# 384X_PWMMOD.net
KiCad netlist of a schematic drawn in Altium Designer
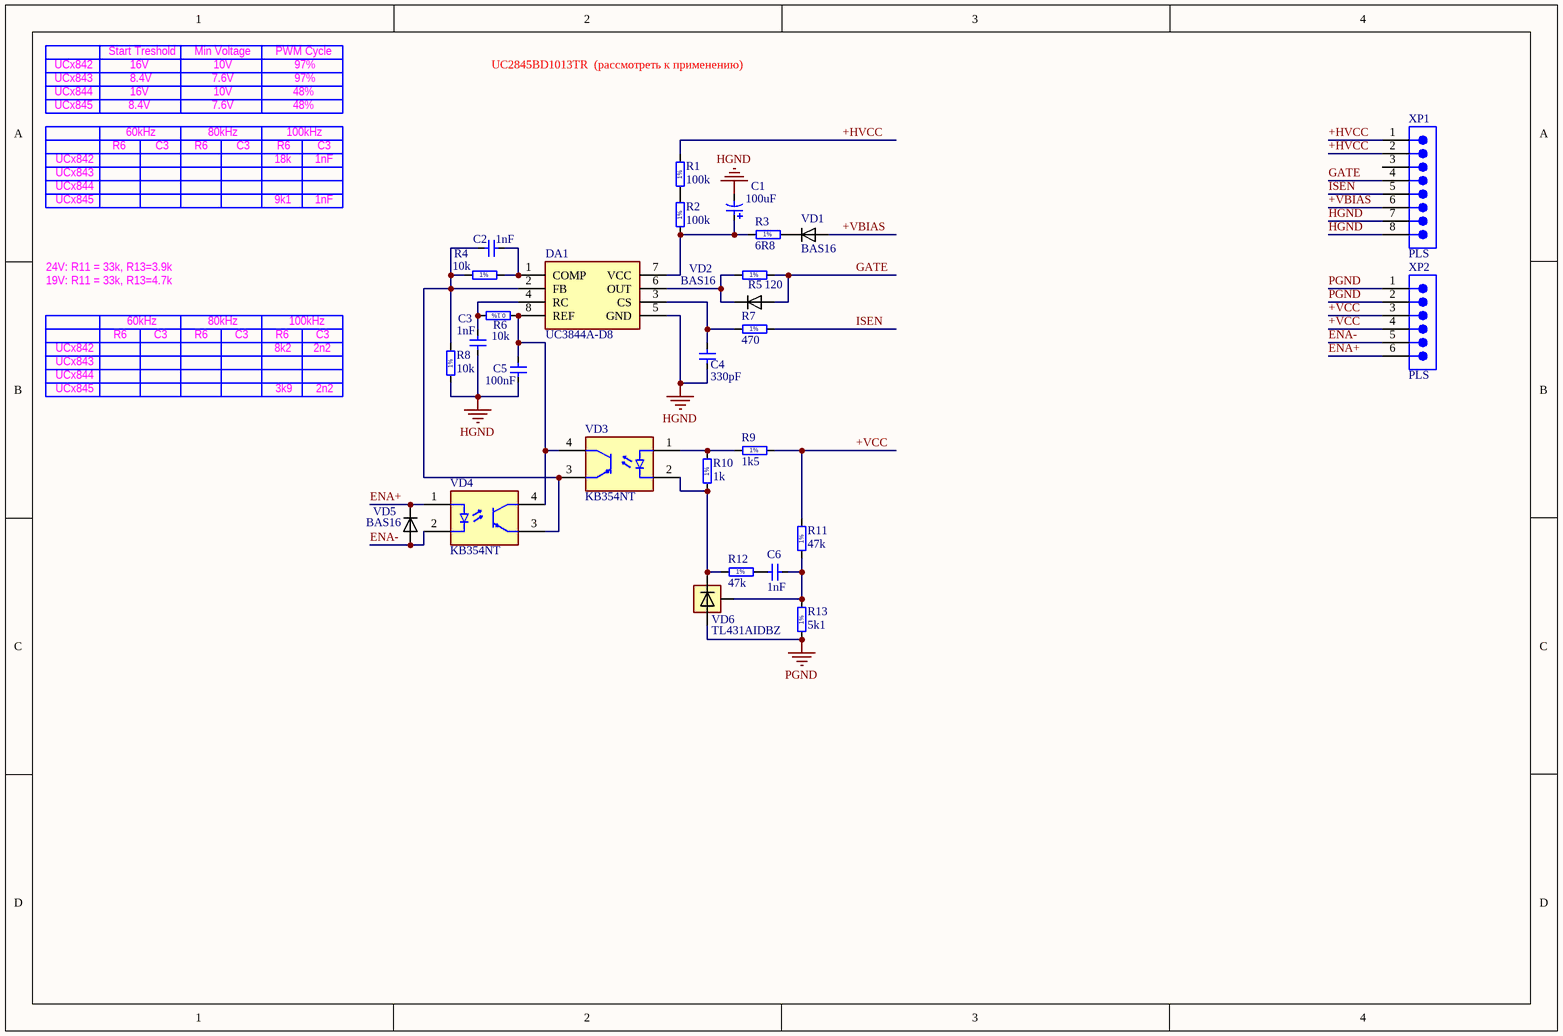
[diagram p0: 384X_PWMMOD.SchDoc]

(export (version "E")
  (design (tool "Eeschema 10.0.6"))
  (components
    (comp (ref "C1")
      (value "100uF")
      (footprint "CAP_EL_06_11_VERT")
      (fields (field (name "PART NUMBER") "SH016M0100BZF-0611 (VERT MOUNTED)") (field (name "VOLTAGE") "16V"))
      (libsource (lib "Capacitor") (part "CAP_POLAR"))
    )
    (comp (ref "C2")
      (value "1nF")
      (footprint "CAP0805R")
      (description "SMD 0805 Capacitor")
      (fields
        (field (name "PART NUMBER") "CC0805_1NF_50V_5%_X7R")
        (field (name "VOLTAGE") "50V")
        (field (name "AUTHOR") "I. Kuznetsov")
      )
      (libsource (lib "Capacitor") (part "CAP_NON_POLAR"))
    )
    (comp (ref "C3")
      (value "1nF")
      (footprint "CAP0805R")
      (description "SMD 0805 Capacitor")
      (fields
        (field (name "PART NUMBER") "CC0805_1NF_50V_5%_X7R")
        (field (name "VOLTAGE") "50V")
        (field (name "AUTHOR") "I. Kuznetsov")
      )
      (libsource (lib "Capacitor") (part "CAP_NON_POLAR"))
    )
    (comp (ref "C4")
      (value "330pF")
      (footprint "CAP0805R")
      (description "SMD 0805 Capacitor")
      (fields
        (field (name "PART NUMBER") "CC0805_330PF_50V_5%_NP0")
        (field (name "VOLTAGE") "50V")
        (field (name "AUTHOR") "I. Kuznetsov")
      )
      (libsource (lib "Capacitor") (part "CAP_NON_POLAR"))
    )
    (comp (ref "C5")
      (value "100nF")
      (footprint "CAP0805R")
      (description "SMD 0805 Capacitor")
      (fields
        (field (name "PART NUMBER") "CC0805_100NF_50V_10%_X7R")
        (field (name "VOLTAGE") "50V")
        (field (name "AUTHOR") "I. Kuznetsov")
      )
      (libsource (lib "Capacitor") (part "CAP_NON_POLAR"))
    )
    (comp (ref "C6")
      (value "1nF")
      (footprint "CAP0805R")
      (description "SMD 0805 Capacitor")
      (fields
        (field (name "PART NUMBER") "CC0805_1NF_50V_5%_X7R")
        (field (name "VOLTAGE") "50V")
        (field (name "AUTHOR") "I. Kuznetsov")
      )
      (libsource (lib "Capacitor") (part "CAP_NON_POLAR"))
    )
    (comp (ref "DA1")
      (value "UC3844A-D8")
      (footprint "SOP8")
      (libsource (lib "IC And Semiconductor") (part "UCX84X"))
    )
    (comp (ref "R1")
      (value "100k")
      (footprint "RES1206R")
      (fields
        (field (name "PART NUMBER") "R1206_100K_1%_0.25W_100PPM")
        (field (name "POWER") "0.25W")
        (field (name "TOLERANCE") "±1%")
        (field (name "AUTHOR") "CERN DEM JLC")
      )
      (libsource (lib "Resistor") (part "Resistor - 1%"))
    )
    (comp (ref "R2")
      (value "100k")
      (footprint "RES1206R")
      (fields
        (field (name "PART NUMBER") "R1206_100K_1%_0.25W_100PPM")
        (field (name "POWER") "0.25W")
        (field (name "TOLERANCE") "±1%")
        (field (name "AUTHOR") "CERN DEM JLC")
      )
      (libsource (lib "Resistor") (part "Resistor - 1%"))
    )
    (comp (ref "R3")
      (value "6R8")
      (footprint "RES0805R")
      (fields
        (field (name "PART NUMBER") "R0805_6R8_1%_0.125W_200PPM")
        (field (name "POWER") "0.125W")
        (field (name "TOLERANCE") "±1%")
        (field (name "AUTHOR") "CERN DEM JLC")
      )
      (libsource (lib "Resistor") (part "Resistor - 1%"))
    )
    (comp (ref "R4")
      (value "10k")
      (footprint "RES0805R")
      (fields
        (field (name "PART NUMBER") "R0805_10K_1%_0.125W_100PPM")
        (field (name "POWER") "0.125W")
        (field (name "TOLERANCE") "±1%")
        (field (name "AUTHOR") "CERN DEM JLC")
      )
      (libsource (lib "Resistor") (part "Resistor - 1%"))
    )
    (comp (ref "R5")
      (value "120")
      (footprint "RES0805R")
      (fields
        (field (name "PART NUMBER") "R0805_120R_1%_0.125W_100PPM")
        (field (name "POWER") "0.125W")
        (field (name "TOLERANCE") "±1%")
        (field (name "AUTHOR") "CERN DEM JLC")
      )
      (libsource (lib "Resistor") (part "Resistor - 1%"))
    )
    (comp (ref "R6")
      (value "10k")
      (footprint "RES0805R")
      (fields
        (field (name "PART NUMBER") "R0805_10K_0.1%_0.1W_10PPM")
        (field (name "POWER") "0.1W")
        (field (name "TOLERANCE") "±0.1%")
        (field (name "AUTHOR") "CERN DEM JLC")
      )
      (libsource (lib "Resistor") (part "Resistor - 0.1%"))
    )
    (comp (ref "R7")
      (value "470")
      (footprint "RES0805R")
      (fields
        (field (name "PART NUMBER") "R0805_470R_1%_0.125W_100PPM")
        (field (name "POWER") "0.125W")
        (field (name "TOLERANCE") "±1%")
        (field (name "AUTHOR") "CERN DEM JLC")
      )
      (libsource (lib "Resistor") (part "Resistor - 1%"))
    )
    (comp (ref "R8")
      (value "10k")
      (footprint "RES0805R")
      (fields
        (field (name "PART NUMBER") "R0805_10K_1%_0.125W_100PPM")
        (field (name "POWER") "0.125W")
        (field (name "TOLERANCE") "±1%")
        (field (name "AUTHOR") "CERN DEM JLC")
      )
      (libsource (lib "Resistor") (part "Resistor - 1%"))
    )
    (comp (ref "R9")
      (value "1k5")
      (footprint "RES0805R")
      (fields
        (field (name "PART NUMBER") "R0805_1K5_1%_0.125W_100PPM")
        (field (name "POWER") "0.125W")
        (field (name "TOLERANCE") "±1%")
        (field (name "AUTHOR") "CERN DEM JLC")
      )
      (libsource (lib "Resistor") (part "Resistor - 1%"))
    )
    (comp (ref "R10")
      (value "1k")
      (footprint "RES0805R")
      (fields
        (field (name "PART NUMBER") "R0805_1K_1%_0.125W_100PPM")
        (field (name "POWER") "0.125W")
        (field (name "TOLERANCE") "±1%")
        (field (name "AUTHOR") "CERN DEM JLC")
      )
      (libsource (lib "Resistor") (part "Resistor - 1%"))
    )
    (comp (ref "R11")
      (value "47k")
      (footprint "RES0805R")
      (fields
        (field (name "PART NUMBER") "R0805_47K_1%_0.125W_100PPM")
        (field (name "POWER") "0.125W")
        (field (name "TOLERANCE") "±1%")
        (field (name "AUTHOR") "CERN DEM JLC")
      )
      (libsource (lib "Resistor") (part "Resistor - 1%"))
    )
    (comp (ref "R12")
      (value "47k")
      (footprint "RES0805R")
      (fields
        (field (name "PART NUMBER") "R0805_47K_1%_0.125W_100PPM")
        (field (name "POWER") "0.125W")
        (field (name "TOLERANCE") "±1%")
        (field (name "AUTHOR") "CERN DEM JLC")
      )
      (libsource (lib "Resistor") (part "Resistor - 1%"))
    )
    (comp (ref "R13")
      (value "5k1")
      (footprint "RES0805R")
      (fields
        (field (name "PART NUMBER") "R0805_5K1_1%_0.125W_100PPM")
        (field (name "POWER") "0.125W")
        (field (name "TOLERANCE") "±1%")
        (field (name "AUTHOR") "CERN DEM JLC")
      )
      (libsource (lib "Resistor") (part "Resistor - 1%"))
    )
    (comp (ref "VD1")
      (value "BAS16")
      (footprint "SOT23")
      (description "Shottky Diode")
      (fields (field (name "PARTNUMBER") "BAS16"))
      (libsource (lib "tda2050") (part "BAS16"))
    )
    (comp (ref "VD2")
      (value "BAS16")
      (footprint "SOT23")
      (libsource (lib "IC And Semiconductor") (part "D_2P_SOT23"))
    )
    (comp (ref "VD3") (value "KB354NT") (footprint "SOP4") (libsource (lib "") (part "xx817_1")))
    (comp (ref "VD4") (value "KB354NT") (footprint "SOP4") (libsource (lib "Optoelectronics") (part "xx817")))
    (comp (ref "VD5")
      (value "BAS16")
      (footprint "SOT23")
      (libsource (lib "IC And Semiconductor") (part "D_2P_SOT23"))
    )
    (comp (ref "VD6")
      (value "TL431AIDBZ")
      (footprint "SOT23")
      (libsource (lib "IC And Semiconductor") (part "Z_3P_SOT23"))
    )
    (comp (ref "XP1")
      (value "PLS")
      (footprint "PLS-08")
      (fields (field (name "PART NUMBER") "PLS-08") (field (name "MANUFACTURER") "AUK"))
      (libsource (lib "Connector") (part "CN_08P_1W"))
    )
    (comp (ref "XP2")
      (value "PLS")
      (footprint "PLS-06")
      (fields (field (name "PART NUMBER") "PLS-06") (field (name "MANUFACTURER") "AUK"))
      (libsource (lib "Connector") (part "CN_06P_1W"))
    )
  )
  (nets
    (net (code "1") (name "/+HVCC") (class "Default")
      (node (ref "R1") (pin "2") (pinfunction "2_2") (pintype "passive"))
      (node (ref "XP1") (pin "1") (pinfunction "1_1") (pintype "passive"))
      (node (ref "XP1") (pin "2") (pinfunction "2_2") (pintype "passive"))
    )
    (net (code "2") (name "/+VBIAS") (class "Default")
      (node (ref "VD1") (pin "1") (pinfunction "A_1") (pintype "passive"))
      (node (ref "XP1") (pin "6") (pinfunction "6_6") (pintype "passive"))
    )
    (net (code "3") (name "/+VCC") (class "Default")
      (node (ref "R11") (pin "2") (pinfunction "2_2") (pintype "passive"))
      (node (ref "R9") (pin "2") (pinfunction "2_2") (pintype "passive"))
      (node (ref "XP2") (pin "3") (pinfunction "3_3") (pintype "passive"))
      (node (ref "XP2") (pin "4") (pinfunction "4_4") (pintype "passive"))
    )
    (net (code "4") (name "/ENA+") (class "Default")
      (node (ref "VD4") (pin "1") (pinfunction "1_1") (pintype "passive"))
      (node (ref "VD5") (pin "3") (pinfunction "K_3") (pintype "passive"))
      (node (ref "XP2") (pin "6") (pinfunction "6_6") (pintype "passive"))
    )
    (net (code "5") (name "/ENA-") (class "Default")
      (node (ref "VD4") (pin "2") (pinfunction "2_2") (pintype "passive"))
      (node (ref "VD5") (pin "1") (pinfunction "A_1") (pintype "passive"))
      (node (ref "XP2") (pin "5") (pinfunction "5_5") (pintype "passive"))
    )
    (net (code "6") (name "/GATE") (class "Default")
      (node (ref "R5") (pin "2") (pinfunction "2_2") (pintype "passive"))
      (node (ref "VD2") (pin "1") (pinfunction "A_1") (pintype "passive"))
      (node (ref "XP1") (pin "4") (pinfunction "4_4") (pintype "passive"))
    )
    (net (code "7") (name "/ISEN") (class "Default")
      (node (ref "R7") (pin "2") (pinfunction "2_2") (pintype "passive"))
      (node (ref "XP1") (pin "5") (pinfunction "5_5") (pintype "passive"))
    )
    (net (code "8") (name "HGND") (class "Default")
      (node (ref "C1") (pin "2") (pinfunction "2_2") (pintype "passive"))
      (node (ref "C3") (pin "1") (pinfunction "1_1") (pintype "passive"))
      (node (ref "C4") (pin "1") (pinfunction "1_1") (pintype "passive"))
      (node (ref "C5") (pin "1") (pinfunction "1_1") (pintype "passive"))
      (node (ref "DA1") (pin "5") (pinfunction "GND_5") (pintype "passive"))
      (node (ref "R8") (pin "1") (pinfunction "1_1") (pintype "passive"))
      (node (ref "XP1") (pin "7") (pinfunction "7_7") (pintype "passive"))
      (node (ref "XP1") (pin "8") (pinfunction "8_8") (pintype "passive"))
    )
    (net (code "9") (name "Net-(C6-Pad1)") (class "Default")
      (node (ref "C6") (pin "1") (pinfunction "1_1") (pintype "passive"))
      (node (ref "R12") (pin "2") (pinfunction "2_2") (pintype "passive"))
    )
    (net (code "10") (name "Net-(DA1-COMP)") (class "Default")
      (node (ref "C2") (pin "2") (pinfunction "2_2") (pintype "passive"))
      (node (ref "DA1") (pin "1") (pinfunction "COMP_1") (pintype "passive"))
      (node (ref "R4") (pin "2") (pinfunction "2_2") (pintype "passive"))
    )
    (net (code "11") (name "Net-(DA1-CS)") (class "Default")
      (node (ref "C4") (pin "2") (pinfunction "2_2") (pintype "passive"))
      (node (ref "DA1") (pin "3") (pinfunction "CS_3") (pintype "passive"))
      (node (ref "R7") (pin "1") (pinfunction "1_1") (pintype "passive"))
    )
    (net (code "12") (name "Net-(DA1-FB)") (class "Default")
      (node (ref "C2") (pin "1") (pinfunction "1_1") (pintype "passive"))
      (node (ref "DA1") (pin "2") (pinfunction "FB_2") (pintype "passive"))
      (node (ref "R4") (pin "1") (pinfunction "1_1") (pintype "passive"))
      (node (ref "R8") (pin "2") (pinfunction "2_2") (pintype "passive"))
      (node (ref "VD3") (pin "3") (pinfunction "E_3") (pintype "passive"))
      (node (ref "VD4") (pin "3") (pinfunction "E_3") (pintype "passive"))
    )
    (net (code "13") (name "Net-(DA1-OUT)") (class "Default")
      (node (ref "DA1") (pin "6") (pinfunction "OUT_6") (pintype "passive"))
      (node (ref "R5") (pin "1") (pinfunction "1_1") (pintype "passive"))
      (node (ref "VD2") (pin "3") (pinfunction "K_3") (pintype "passive"))
    )
    (net (code "14") (name "Net-(DA1-RC)") (class "Default")
      (node (ref "C3") (pin "2") (pinfunction "2_2") (pintype "passive"))
      (node (ref "DA1") (pin "4") (pinfunction "RC_4") (pintype "passive"))
      (node (ref "R6") (pin "2") (pinfunction "2_2") (pintype "passive"))
    )
    (net (code "15") (name "Net-(DA1-REF)") (class "Default")
      (node (ref "C5") (pin "2") (pinfunction "2_2") (pintype "passive"))
      (node (ref "DA1") (pin "8") (pinfunction "REF_8") (pintype "passive"))
      (node (ref "R6") (pin "1") (pinfunction "1_1") (pintype "passive"))
      (node (ref "VD3") (pin "4") (pinfunction "C_4") (pintype "passive"))
      (node (ref "VD4") (pin "4") (pinfunction "C_4") (pintype "passive"))
    )
    (net (code "16") (name "Net-(DA1-VCC)") (class "Default")
      (node (ref "C1") (pin "1") (pinfunction "1_1") (pintype "passive"))
      (node (ref "DA1") (pin "7") (pinfunction "VCC_7") (pintype "passive"))
      (node (ref "R2") (pin "1") (pinfunction "1_1") (pintype "passive"))
      (node (ref "R3") (pin "1") (pinfunction "1_1") (pintype "passive"))
    )
    (net (code "17") (name "Net-(R1-Pad1)") (class "Default")
      (node (ref "R1") (pin "1") (pinfunction "1_1") (pintype "passive"))
      (node (ref "R2") (pin "2") (pinfunction "2_2") (pintype "passive"))
    )
    (net (code "18") (name "Net-(R10-Pad2)") (class "Default")
      (node (ref "R10") (pin "2") (pinfunction "2_2") (pintype "passive"))
      (node (ref "R9") (pin "1") (pinfunction "1_1") (pintype "passive"))
      (node (ref "VD3") (pin "1") (pinfunction "1_1") (pintype "passive"))
    )
    (net (code "19") (name "Net-(VD1-K)") (class "Default")
      (node (ref "R3") (pin "2") (pinfunction "2_2") (pintype "passive"))
      (node (ref "VD1") (pin "3") (pinfunction "K_3") (pintype "passive"))
    )
    (net (code "20") (name "Net-(VD6-K)") (class "Default")
      (node (ref "R10") (pin "1") (pinfunction "1_1") (pintype "passive"))
      (node (ref "R12") (pin "1") (pinfunction "1_1") (pintype "passive"))
      (node (ref "VD3") (pin "2") (pinfunction "2_2") (pintype "passive"))
      (node (ref "VD6") (pin "1") (pinfunction "K_1") (pintype "passive"))
    )
    (net (code "21") (name "Net-(VD6-REF)") (class "Default")
      (node (ref "C6") (pin "2") (pinfunction "2_2") (pintype "passive"))
      (node (ref "R11") (pin "1") (pinfunction "1_1") (pintype "passive"))
      (node (ref "R13") (pin "2") (pinfunction "2_2") (pintype "passive"))
      (node (ref "VD6") (pin "2") (pinfunction "REF_2") (pintype "passive"))
    )
    (net (code "22") (name "PGND") (class "Default")
      (node (ref "R13") (pin "1") (pinfunction "1_1") (pintype "passive"))
      (node (ref "VD6") (pin "3") (pinfunction "A_3") (pintype "passive"))
      (node (ref "XP2") (pin "1") (pinfunction "1_1") (pintype "passive"))
      (node (ref "XP2") (pin "2") (pinfunction "2_2") (pintype "passive"))
    )
    (net (code "23") (name "unconnected-(XP1-Pad3)") (class "Default")
      (node (ref "XP1") (pin "3") (pinfunction "3_3") (pintype "passive"))
    )
  )
)
